# MCU.net
KiCad netlist of a schematic drawn in Altium Designer
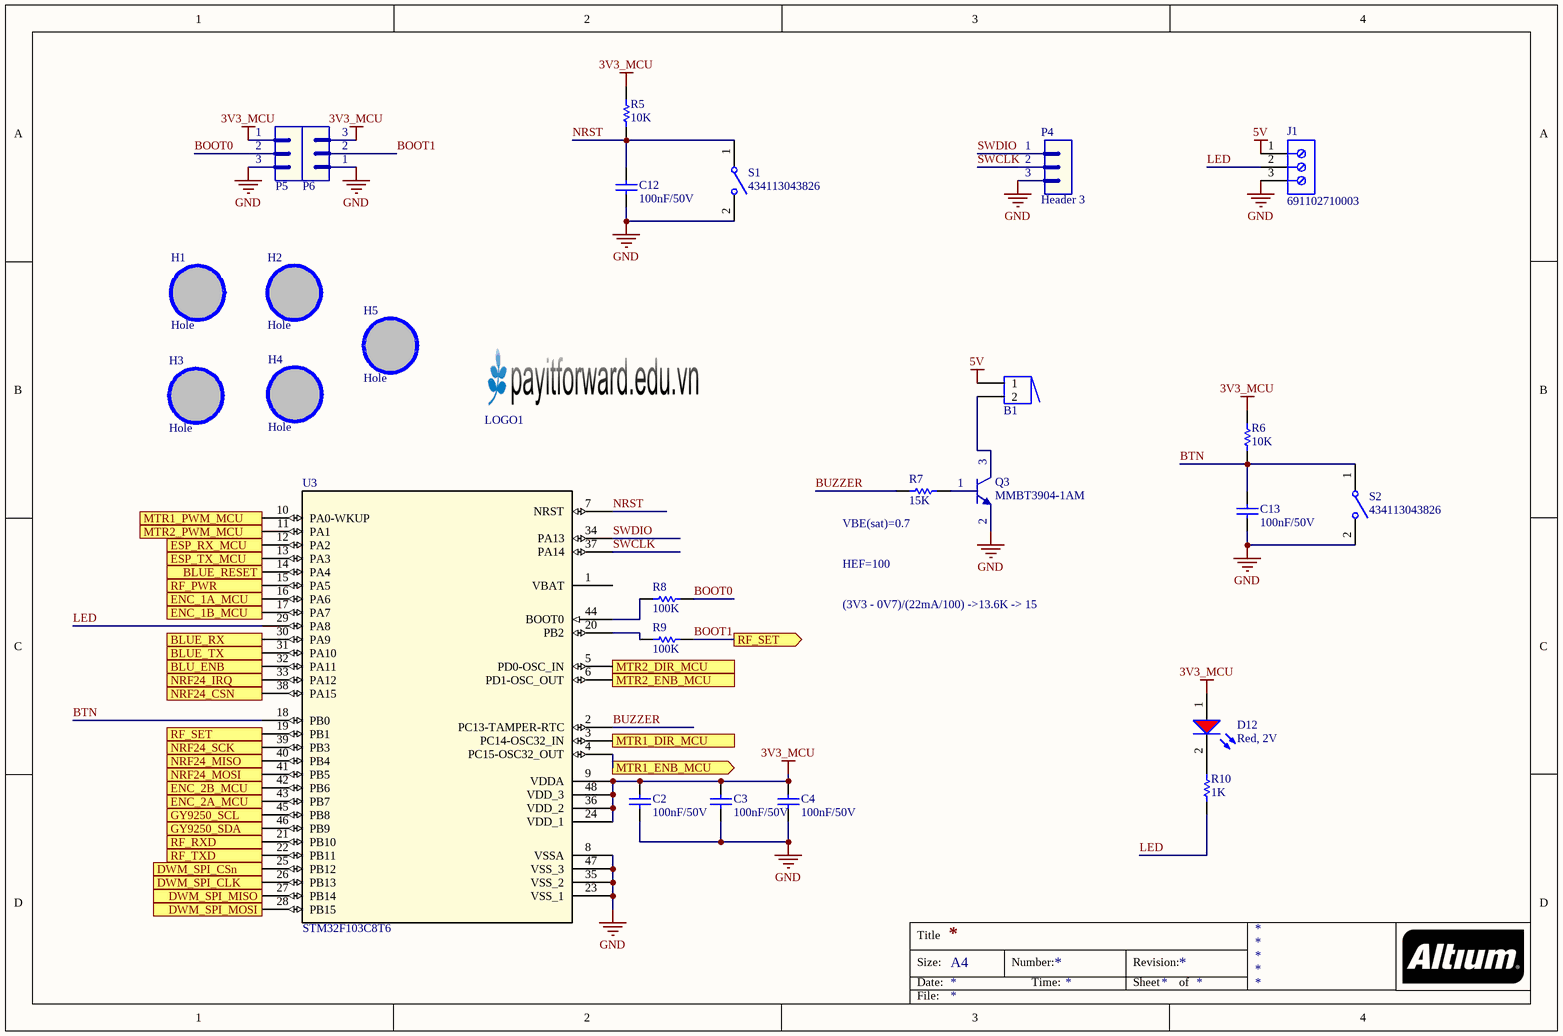
[diagram p0: MCU.schdoc]

(export (version "E")
  (design (tool "Eeschema 10.0.6"))
  (components
    (comp (ref "B1")
      (value "Buzzer")
      (footprint "BUZZER")
      (libsource (lib "PIF_Schematic_Lib") (part "Buzzer"))
    )
    (comp (ref "C2")
      (value "100nF/50V")
      (footprint "CAP-SM-0805")
      (description "CAP CER 0.1UF 50V Y5V 0805")
      (fields
        (field (name "MANUFACTURER") "Samsung Electro-Mechanics")
        (field (name "MANUFACTURER PART NUMBER") "CL21F104ZBCNNNC")
      )
      (libsource (lib "Capacitor") (part "Cap-100nF-50V-0805"))
    )
    (comp (ref "C3")
      (value "100nF/50V")
      (footprint "CAP-SM-0805")
      (description "CAP CER 0.1UF 50V Y5V 0805")
      (fields
        (field (name "MANUFACTURER") "Samsung Electro-Mechanics")
        (field (name "MANUFACTURER PART NUMBER") "CL21F104ZBCNNNC")
      )
      (libsource (lib "Capacitor") (part "Cap-100nF-50V-0805"))
    )
    (comp (ref "C4")
      (value "100nF/50V")
      (footprint "CAP-SM-0805")
      (description "CAP CER 0.1UF 50V Y5V 0805")
      (fields
        (field (name "MANUFACTURER") "Samsung Electro-Mechanics")
        (field (name "MANUFACTURER PART NUMBER") "CL21F104ZBCNNNC")
      )
      (libsource (lib "Capacitor") (part "Cap-100nF-50V-0805"))
    )
    (comp (ref "C12")
      (value "100nF/50V")
      (footprint "CAP-SM-0805")
      (description "CAP CER 0.1UF 50V Y5V 0805")
      (fields
        (field (name "MANUFACTURER") "Samsung Electro-Mechanics")
        (field (name "MANUFACTURER PART NUMBER") "CL21F104ZBCNNNC")
      )
      (libsource (lib "Capacitor") (part "Cap-100nF-50V-0805"))
    )
    (comp (ref "C13")
      (value "100nF/50V")
      (footprint "CAP-SM-0805")
      (description "CAP CER 0.1UF 50V Y5V 0805")
      (fields
        (field (name "MANUFACTURER") "Samsung Electro-Mechanics")
        (field (name "MANUFACTURER PART NUMBER") "CL21F104ZBCNNNC")
      )
      (libsource (lib "Capacitor") (part "Cap-100nF-50V-0805"))
    )
    (comp (ref "D12")
      (value "Red, 2V")
      (footprint "LED-3mm")
      (description "LED RED CLEAR T-1 T/H")
      (fields
        (field (name "MANUFACTURER") "Kingbright")
        (field (name "MANUFACTURER PART NUMBER") "WP710A10SEC/J3")
      )
      (libsource (lib "LED") (part "LED-RED-TH-3mm"))
    )
    (comp (ref "H1")
      (value "Hole")
      (footprint "LO KHOAN 3MM")
      (description "Hole 3mm")
      (libsource (lib "PIF_C16_lib") (part "Hole"))
    )
    (comp (ref "H2")
      (value "Hole")
      (footprint "LO KHOAN 3MM")
      (description "Hole 3mm")
      (libsource (lib "PIF_C16_lib") (part "Hole"))
    )
    (comp (ref "H3")
      (value "Hole")
      (footprint "LO KHOAN 3MM")
      (description "Hole 3mm")
      (libsource (lib "PIF_C16_lib") (part "Hole"))
    )
    (comp (ref "H4")
      (value "Hole")
      (footprint "LO KHOAN 3MM")
      (description "Hole 3mm")
      (libsource (lib "PIF_C16_lib") (part "Hole"))
    )
    (comp (ref "H5")
      (value "Hole")
      (footprint "LO KHOAN 3MM")
      (description "Hole 3mm")
      (libsource (lib "PIF_C16_lib") (part "Hole"))
    )
    (comp (ref "J1")
      (value "691102710003")
      (footprint "691102710003")
      (description "WR-TBL Serie 102 Horizontal Entry Modular, Pressure Clamp, pitch 5mm, 3p")
      (fields (field (name "PUBLISHER") "Wurth Elektronik"))
      (libsource (lib "691101710002_Altium_WR-TBL_rev19a") (part "691102710003"))
    )
    (comp (ref "LOGO1")
      (value "LOGO PIF")
      (footprint "PIF LOGO BIG SSTOP")
      (libsource (lib "PIF_C16_lib") (part "LOGO PIF"))
    )
    (comp (ref "P4")
      (value "Header 3")
      (footprint "JP3")
      (description "Header, 3-Pin")
      (fields (field (name "PUBLISHER") "Altium Limited"))
      (libsource (lib "") (part "Header 3_1"))
    )
    (comp (ref "P5")
      (value "Header 3")
      (footprint "JP3")
      (description "Header, 3-Pin")
      (fields (field (name "PUBLISHER") "Altium Limited"))
      (libsource (lib "") (part "Header 3_1"))
    )
    (comp (ref "P6")
      (value "Header 3")
      (footprint "JP3")
      (description "Header, 3-Pin")
      (fields (field (name "PUBLISHER") "Altium Limited"))
      (libsource (lib "PIF_C16_lib") (part "Header 3"))
    )
    (comp (ref "Q3")
      (value "MMBT3904-1AM")
      (footprint "BJT:SOT23_NEX")
      (libsource (lib "BJT") (part "MMBT3904-1AM"))
    )
    (comp (ref "R5")
      (value "10K")
      (footprint "Resistor:RES-SM-0805")
      (description "RES 10K OHM 1% 1/4W 0805")
      (fields
        (field (name "MANUFACTURER") "Stackpole Electronics Inc")
        (field (name "MANUFACTURER PART NUMBER") "RNCP0805FTD10K0")
      )
      (libsource (lib "Resistor") (part "Res-10k-0805"))
    )
    (comp (ref "R6")
      (value "10K")
      (footprint "Resistor:RES-SM-0805")
      (description "RES 10K OHM 1% 1/4W 0805")
      (fields
        (field (name "MANUFACTURER") "Stackpole Electronics Inc")
        (field (name "MANUFACTURER PART NUMBER") "RNCP0805FTD10K0")
      )
      (libsource (lib "Resistor") (part "Res-10k-0805"))
    )
    (comp (ref "R7")
      (value "15K")
      (footprint "Resistor:RES-SM-0805")
      (description "RES 15K OHM 1% 1/4W 0805")
      (fields
        (field (name "MANUFACTURER") "TE Connectivity Passive Product")
        (field (name "MANUFACTURER PART NUMBER") "CRGCQ0805F15K")
      )
      (libsource (lib "Resistor") (part "Res-15K-0805"))
    )
    (comp (ref "R8")
      (value "100K")
      (footprint "Resistor:RES-SM-0805")
      (description "RES 0 OHM JUMPER 0805")
      (fields
        (field (name "MANUFACTURER") "Vishay Dale")
        (field (name "MANUFACTURER PART NUMBER") "WSL080500000ZEA9")
      )
      (libsource (lib "Resistor") (part "Res-100K-0805"))
    )
    (comp (ref "R9")
      (value "100K")
      (footprint "Resistor:RES-SM-0805")
      (description "RES 0 OHM JUMPER 0805")
      (fields
        (field (name "MANUFACTURER") "Vishay Dale")
        (field (name "MANUFACTURER PART NUMBER") "WSL080500000ZEA9")
      )
      (libsource (lib "Resistor") (part "Res-100K-0805"))
    )
    (comp (ref "R10")
      (value "1K")
      (footprint "Resistor:RES-SM-0805")
      (description "RES 1K OHM 1% 1/4W 0805")
      (fields
        (field (name "MANUFACTURER") "Stackpole Electronics Inc")
        (field (name "MANUFACTURER PART NUMBER") "RNCP0805FTD1K00")
      )
      (libsource (lib "Resistor") (part "Res-1K-0805"))
    )
    (comp (ref "S1")
      (value "434113043826")
      (footprint "434113043826")
      (description "WS-TASV J-Bend SMT Tact Switch 6x3.5mm, height 4.3mm, 260gf")
      (fields (field (name "PUBLISHER") "Wurth Elektronik"))
      (libsource (lib "434113043826_Altium_WS-TASV_rev20a") (part "434113043826"))
    )
    (comp (ref "S2")
      (value "434113043826")
      (footprint "434113043826")
      (description "WS-TASV J-Bend SMT Tact Switch 6x3.5mm, height 4.3mm, 260gf")
      (fields (field (name "PUBLISHER") "Wurth Elektronik"))
      (libsource (lib "434113043826_Altium_WS-TASV_rev20a") (part "434113043826"))
    )
    (comp (ref "U3")
      (value "STM32F103C8T6")
      (footprint "LQFP-48")
      (description "No Description Available")
      (fields (field (name "COPYRIGHT") "Copyright (C) 2018 Accelerated Designs. All rights reserved"))
      (libsource (lib "Bai1") (part "STM32F103C8T6"))
    )
  )
  (nets
    (net (code "1") (name "/BLUE_RESET") (class "Default")
      (node (ref "U3") (pin "14") (pinfunction "PA4_14") (pintype "bidirectional"))
    )
    (net (code "2") (name "/BLUE_RX") (class "Default")
      (node (ref "U3") (pin "30") (pinfunction "PA9_30") (pintype "bidirectional"))
    )
    (net (code "3") (name "/BLUE_TX") (class "Default")
      (node (ref "U3") (pin "31") (pinfunction "PA10_31") (pintype "bidirectional"))
    )
    (net (code "4") (name "/BLU_ENB") (class "Default")
      (node (ref "U3") (pin "32") (pinfunction "PA11_32") (pintype "bidirectional"))
    )
    (net (code "5") (name "/BOOT0") (class "Default")
      (node (ref "P5") (pin "2") (pinfunction "2_2") (pintype "passive"))
      (node (ref "R8") (pin "2") (pinfunction "2_2") (pintype "passive"))
    )
    (net (code "6") (name "/BOOT1") (class "Default")
      (node (ref "P6") (pin "2") (pinfunction "2_2") (pintype "passive"))
      (node (ref "R9") (pin "2") (pinfunction "2_2") (pintype "passive"))
      (node (ref "U3") (pin "19") (pinfunction "PB1_19") (pintype "bidirectional"))
    )
    (net (code "7") (name "/BTN") (class "Default")
      (node (ref "C13") (pin "2") (pinfunction "2_2") (pintype "passive"))
      (node (ref "R6") (pin "1") (pinfunction "1_1") (pintype "passive"))
      (node (ref "S2") (pin "1") (pinfunction "1_1") (pintype "passive"))
      (node (ref "U3") (pin "18") (pinfunction "PB0_18") (pintype "bidirectional"))
    )
    (net (code "8") (name "/BUZZER") (class "Default")
      (node (ref "R7") (pin "1") (pinfunction "1_1") (pintype "passive"))
      (node (ref "U3") (pin "2") (pinfunction "PC13-TAMPER-RTC_2") (pintype "bidirectional"))
    )
    (net (code "9") (name "/DWM_SPI_CLK") (class "Default")
      (node (ref "U3") (pin "26") (pinfunction "PB13_26") (pintype "bidirectional"))
    )
    (net (code "10") (name "/DWM_SPI_CSn") (class "Default")
      (node (ref "U3") (pin "25") (pinfunction "PB12_25") (pintype "bidirectional"))
    )
    (net (code "11") (name "/DWM_SPI_MISO") (class "Default")
      (node (ref "U3") (pin "27") (pinfunction "PB14_27") (pintype "bidirectional"))
    )
    (net (code "12") (name "/DWM_SPI_MOSI") (class "Default")
      (node (ref "U3") (pin "28") (pinfunction "PB15_28") (pintype "bidirectional"))
    )
    (net (code "13") (name "/ENC_1A_MCU") (class "Default")
      (node (ref "U3") (pin "16") (pinfunction "PA6_16") (pintype "bidirectional"))
    )
    (net (code "14") (name "/ENC_1B_MCU") (class "Default")
      (node (ref "U3") (pin "17") (pinfunction "PA7_17") (pintype "bidirectional"))
    )
    (net (code "15") (name "/ENC_2A_MCU") (class "Default")
      (node (ref "U3") (pin "43") (pinfunction "PB7_43") (pintype "bidirectional"))
    )
    (net (code "16") (name "/ENC_2B_MCU") (class "Default")
      (node (ref "U3") (pin "42") (pinfunction "PB6_42") (pintype "bidirectional"))
    )
    (net (code "17") (name "/ESP_RX_MCU") (class "Default")
      (node (ref "U3") (pin "12") (pinfunction "PA2_12") (pintype "bidirectional"))
    )
    (net (code "18") (name "/ESP_TX_MCU") (class "Default")
      (node (ref "U3") (pin "13") (pinfunction "PA3_13") (pintype "bidirectional"))
    )
    (net (code "19") (name "/GY9250_SCL") (class "Default")
      (node (ref "U3") (pin "45") (pinfunction "PB8_45") (pintype "bidirectional"))
    )
    (net (code "20") (name "/GY9250_SDA") (class "Default")
      (node (ref "U3") (pin "46") (pinfunction "PB9_46") (pintype "bidirectional"))
    )
    (net (code "21") (name "/LED") (class "Default")
      (node (ref "J1") (pin "2") (pinfunction "2_2") (pintype "passive"))
      (node (ref "R10") (pin "1") (pinfunction "1_1") (pintype "passive"))
      (node (ref "U3") (pin "29") (pinfunction "PA8_29") (pintype "bidirectional"))
    )
    (net (code "22") (name "/MTR1_DIR_MCU") (class "Default")
      (node (ref "U3") (pin "3") (pinfunction "PC14-OSC32_IN_3") (pintype "bidirectional"))
    )
    (net (code "23") (name "/MTR1_ENB_MCU") (class "Default")
      (node (ref "U3") (pin "4") (pinfunction "PC15-OSC32_OUT_4") (pintype "bidirectional"))
    )
    (net (code "24") (name "/MTR1_PWM_MCU") (class "Default")
      (node (ref "U3") (pin "10") (pinfunction "PA0-WKUP_10") (pintype "bidirectional"))
    )
    (net (code "25") (name "/MTR2_DIR_MCU") (class "Default")
      (node (ref "U3") (pin "5") (pinfunction "PD0-OSC_IN_5") (pintype "bidirectional"))
    )
    (net (code "26") (name "/MTR2_ENB_MCU") (class "Default")
      (node (ref "U3") (pin "6") (pinfunction "PD1-OSC_OUT_6") (pintype "bidirectional"))
    )
    (net (code "27") (name "/MTR2_PWM_MCU") (class "Default")
      (node (ref "U3") (pin "11") (pinfunction "PA1_11") (pintype "bidirectional"))
    )
    (net (code "28") (name "/NRF24_CSN") (class "Default")
      (node (ref "U3") (pin "38") (pinfunction "PA15_38") (pintype "bidirectional"))
    )
    (net (code "29") (name "/NRF24_IRQ") (class "Default")
      (node (ref "U3") (pin "33") (pinfunction "PA12_33") (pintype "bidirectional"))
    )
    (net (code "30") (name "/NRF24_MISO") (class "Default")
      (node (ref "U3") (pin "40") (pinfunction "PB4_40") (pintype "bidirectional"))
    )
    (net (code "31") (name "/NRF24_MOSI") (class "Default")
      (node (ref "U3") (pin "41") (pinfunction "PB5_41") (pintype "bidirectional"))
    )
    (net (code "32") (name "/NRF24_SCK") (class "Default")
      (node (ref "U3") (pin "39") (pinfunction "PB3_39") (pintype "bidirectional"))
    )
    (net (code "33") (name "/NRST") (class "Default")
      (node (ref "C12") (pin "2") (pinfunction "2_2") (pintype "passive"))
      (node (ref "R5") (pin "1") (pinfunction "1_1") (pintype "passive"))
      (node (ref "S1") (pin "1") (pinfunction "1_1") (pintype "passive"))
      (node (ref "U3") (pin "7") (pinfunction "NRST_7") (pintype "bidirectional"))
    )
    (net (code "34") (name "/RF_PWR") (class "Default")
      (node (ref "U3") (pin "15") (pinfunction "PA5_15") (pintype "bidirectional"))
    )
    (net (code "35") (name "/RF_RXD") (class "Default")
      (node (ref "U3") (pin "21") (pinfunction "PB10_21") (pintype "bidirectional"))
    )
    (net (code "36") (name "/RF_TXD") (class "Default")
      (node (ref "U3") (pin "22") (pinfunction "PB11_22") (pintype "bidirectional"))
    )
    (net (code "37") (name "/SWCLK") (class "Default")
      (node (ref "P4") (pin "2") (pinfunction "2_2") (pintype "passive"))
      (node (ref "U3") (pin "37") (pinfunction "PA14_37") (pintype "bidirectional"))
    )
    (net (code "38") (name "/SWDIO") (class "Default")
      (node (ref "P4") (pin "1") (pinfunction "1_1") (pintype "passive"))
      (node (ref "U3") (pin "34") (pinfunction "PA13_34") (pintype "bidirectional"))
    )
    (net (code "39") (name "3V3_MCU") (class "Default")
      (node (ref "C2") (pin "2") (pinfunction "2_2") (pintype "passive"))
      (node (ref "C3") (pin "2") (pinfunction "2_2") (pintype "passive"))
      (node (ref "C4") (pin "2") (pinfunction "2_2") (pintype "passive"))
      (node (ref "D12") (pin "1") (pinfunction "A_1") (pintype "passive"))
      (node (ref "P5") (pin "1") (pinfunction "1_1") (pintype "passive"))
      (node (ref "P6") (pin "3") (pinfunction "3_3") (pintype "passive"))
      (node (ref "R5") (pin "2") (pinfunction "2_2") (pintype "passive"))
      (node (ref "R6") (pin "2") (pinfunction "2_2") (pintype "passive"))
      (node (ref "U3") (pin "24") (pinfunction "VDD_1_24") (pintype "passive"))
      (node (ref "U3") (pin "36") (pinfunction "VDD_2_36") (pintype "power_in"))
      (node (ref "U3") (pin "48") (pinfunction "VDD_3_48") (pintype "passive"))
      (node (ref "U3") (pin "9") (pinfunction "VDDA_9") (pintype "passive"))
    )
    (net (code "40") (name "5V") (class "Default")
      (node (ref "B1") (pin "1") (pinfunction "1_1") (pintype "passive"))
      (node (ref "J1") (pin "1") (pinfunction "1_1") (pintype "passive"))
    )
    (net (code "41") (name "GND") (class "Default")
      (node (ref "C12") (pin "1") (pinfunction "1_1") (pintype "passive"))
      (node (ref "C13") (pin "1") (pinfunction "1_1") (pintype "passive"))
      (node (ref "C2") (pin "1") (pinfunction "1_1") (pintype "passive"))
      (node (ref "C3") (pin "1") (pinfunction "1_1") (pintype "passive"))
      (node (ref "C4") (pin "1") (pinfunction "1_1") (pintype "passive"))
      (node (ref "J1") (pin "3") (pinfunction "3_3") (pintype "passive"))
      (node (ref "P4") (pin "3") (pinfunction "3_3") (pintype "passive"))
      (node (ref "P5") (pin "3") (pinfunction "3_3") (pintype "passive"))
      (node (ref "P6") (pin "1") (pinfunction "1_1") (pintype "passive"))
      (node (ref "Q3") (pin "2") (pinfunction "E_2") (pintype "passive"))
      (node (ref "S1") (pin "2") (pinfunction "2_2") (pintype "passive"))
      (node (ref "S2") (pin "2") (pinfunction "2_2") (pintype "passive"))
      (node (ref "U3") (pin "23") (pinfunction "VSS_1_23") (pintype "passive"))
      (node (ref "U3") (pin "35") (pinfunction "VSS_2_35") (pintype "passive"))
      (node (ref "U3") (pin "47") (pinfunction "VSS_3_47") (pintype "passive"))
      (node (ref "U3") (pin "8") (pinfunction "VSSA_8") (pintype "passive"))
    )
    (net (code "42") (name "Net-(D12-K)") (class "Default")
      (node (ref "D12") (pin "2") (pinfunction "K_2") (pintype "passive"))
      (node (ref "R10") (pin "2") (pinfunction "2_2") (pintype "passive"))
    )
    (net (code "43") (name "Net-(Q3-B)") (class "Default")
      (node (ref "Q3") (pin "1") (pinfunction "B_1") (pintype "passive"))
      (node (ref "R7") (pin "2") (pinfunction "2_2") (pintype "passive"))
    )
    (net (code "44") (name "Net-(Q3-C)") (class "Default")
      (node (ref "B1") (pin "2") (pinfunction "2_2") (pintype "passive"))
      (node (ref "Q3") (pin "3") (pinfunction "C_3") (pintype "passive"))
    )
    (net (code "45") (name "Net-(U3-BOOT0)") (class "Default")
      (node (ref "R8") (pin "1") (pinfunction "1_1") (pintype "passive"))
      (node (ref "U3") (pin "44") (pinfunction "BOOT0_44") (pintype "input"))
    )
    (net (code "46") (name "Net-(U3-PB2)") (class "Default")
      (node (ref "R9") (pin "1") (pinfunction "1_1") (pintype "passive"))
      (node (ref "U3") (pin "20") (pinfunction "PB2_20") (pintype "bidirectional"))
    )
    (net (code "47") (name "unconnected-(H1-Pad1)") (class "Default")
      (node (ref "H1") (pin "1") (pinfunction "1_1") (pintype "passive"))
    )
    (net (code "48") (name "unconnected-(H2-Pad1)") (class "Default")
      (node (ref "H2") (pin "1") (pinfunction "1_1") (pintype "passive"))
    )
    (net (code "49") (name "unconnected-(H3-Pad1)") (class "Default")
      (node (ref "H3") (pin "1") (pinfunction "1_1") (pintype "passive"))
    )
    (net (code "50") (name "unconnected-(H4-Pad1)") (class "Default")
      (node (ref "H4") (pin "1") (pinfunction "1_1") (pintype "passive"))
    )
    (net (code "51") (name "unconnected-(H5-Pad1)") (class "Default")
      (node (ref "H5") (pin "1") (pinfunction "1_1") (pintype "passive"))
    )
    (net (code "52") (name "unconnected-(U3-VBAT-Pad1)") (class "Default")
      (node (ref "U3") (pin "1") (pinfunction "VBAT_1") (pintype "power_in"))
    )
  )
)
